# All.net
KiCad netlist of a schematic drawn in EAGLE
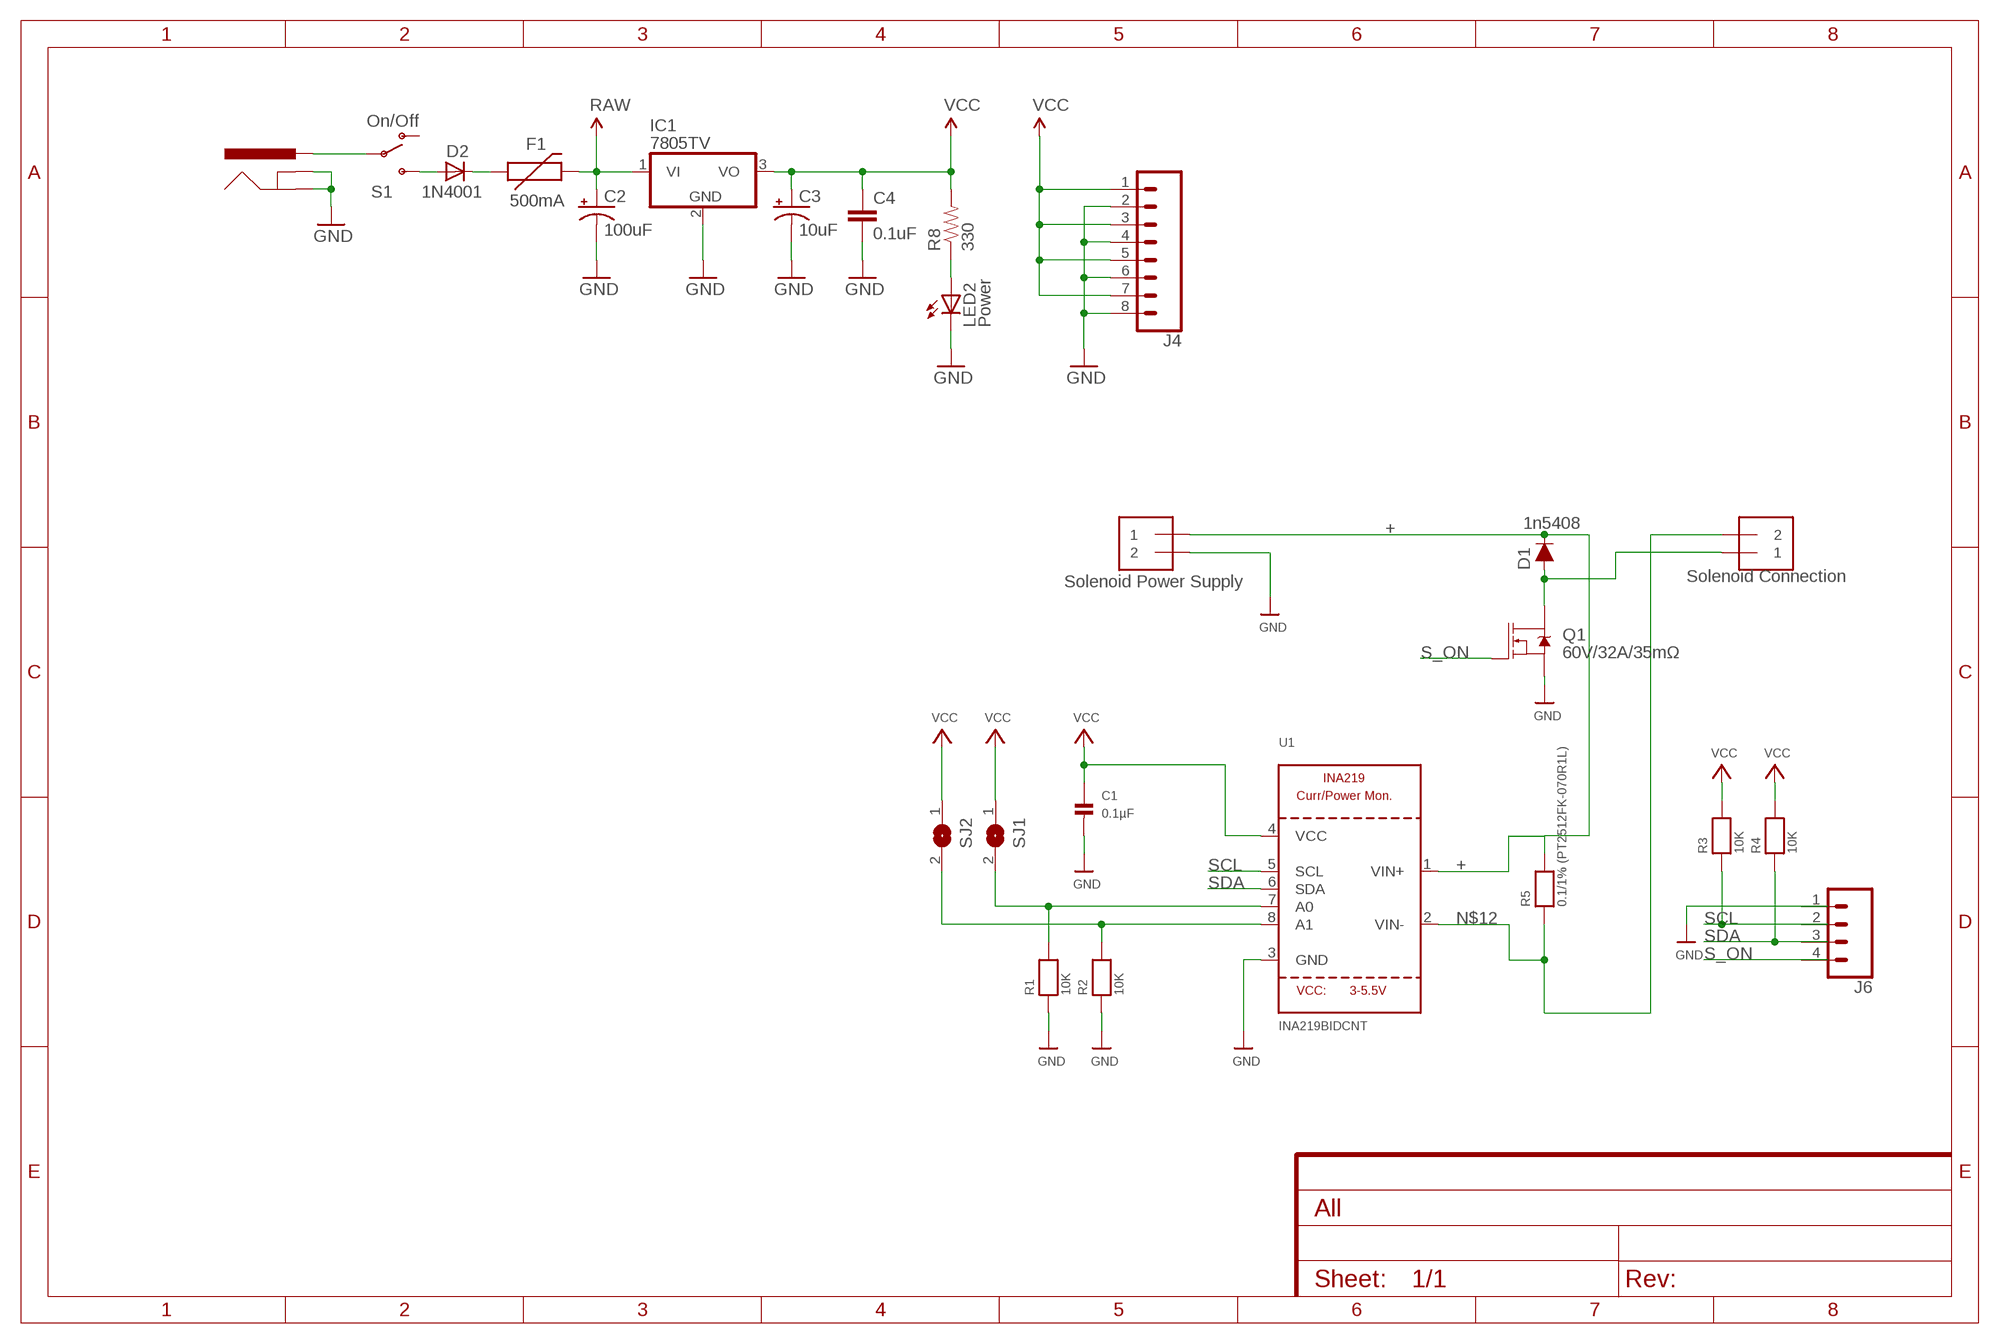
[diagram p0: schematic, sheet 1]

(export (version "E")
  (design (tool "Eeschema 10.0.6"))
  (components
    (comp (ref "C1")
      (value "0.1µF")
      (footprint "eagle-import:0805")
      (libsource (lib "eagle-import") (part "CAP_CERAMIC0805"))
    )
    (comp (ref "C2")
      (value "100uF")
      (footprint "eagle-import:CPOL-RADIAL-100UF-25V")
      (libsource (lib "eagle-import") (part "CAP_POLPTH1"))
    )
    (comp (ref "C3")
      (value "10uF")
      (footprint "eagle-import:CPOL-RADIAL-10UF-25V")
      (libsource (lib "eagle-import") (part "CAP_POLPTH2"))
    )
    (comp (ref "C4")
      (value "0.1uF")
      (footprint "eagle-import:CAP-PTH-SMALL2")
      (libsource (lib "eagle-import") (part "CAPPTH2"))
    )
    (comp (ref "D1")
      (value "DIODE-1N4148")
      (footprint "eagle-import:DIODE-1N4148")
      (fields (field (name "TEMP") "1n5408"))
      (libsource (lib "eagle-import") (part "DIODE-1N4148"))
    )
    (comp (ref "D2")
      (value "1N4001")
      (footprint "eagle-import:DIODE-0.4")
      (libsource (lib "eagle-import") (part "DIODEPTH"))
    )
    (comp (ref "F1")
      (value "500mA")
      (footprint "eagle-import:PTC")
      (libsource (lib "eagle-import") (part "PTCPTH"))
    )
    (comp (ref "IC1")
      (value "7805TV")
      (footprint "eagle-import:TO220V")
      (libsource (lib "eagle-import") (part "78TV05"))
    )
    (comp (ref "J1")
      (value "POWER_JACKPTH")
      (footprint "eagle-import:POWER_JACK_PTH")
      (libsource (lib "eagle-import") (part "POWER_JACKPTH"))
    )
    (comp (ref "J2")
      (value "TERMBLOCK_1X2-3.5MM")
      (footprint "eagle-import:1X2-3.5MM")
      (fields (field (name "TEMP") "Solenoid Power Supply"))
      (libsource (lib "eagle-import") (part "TERMBLOCK_1X2-3.5MM"))
    )
    (comp (ref "J3")
      (value "TERMBLOCK_1X2-3.5MM")
      (footprint "eagle-import:1X2-3.5MM")
      (fields (field (name "TEMP") "Solenoid Connection"))
      (libsource (lib "eagle-import") (part "TERMBLOCK_1X2-3.5MM"))
    )
    (comp (ref "J4")
      (value "CONN_08\"")
      (footprint "eagle-import:1X08")
      (libsource (lib "eagle-import") (part "CONN_08{dblquote}"))
    )
    (comp (ref "J6")
      (value "CONN_04")
      (footprint "eagle-import:1X04")
      (libsource (lib "eagle-import") (part "CONN_04"))
    )
    (comp (ref "LED2")
      (value "Power")
      (footprint "eagle-import:LED5MM")
      (libsource (lib "eagle-import") (part "LED5MM"))
    )
    (comp (ref "Q1")
      (value "60V/32A/35mΩ")
      (footprint "eagle-import:TO220V")
      (libsource (lib "eagle-import") (part "MOSFET-NCH-FQP30N06L"))
    )
    (comp (ref "R1")
      (value "10K")
      (footprint "eagle-import:0805")
      (libsource (lib "eagle-import") (part "RESISTOR0805"))
    )
    (comp (ref "R2")
      (value "10K")
      (footprint "eagle-import:0805")
      (libsource (lib "eagle-import") (part "RESISTOR0805"))
    )
    (comp (ref "R3")
      (value "10K")
      (footprint "eagle-import:0805")
      (libsource (lib "eagle-import") (part "RESISTOR0805"))
    )
    (comp (ref "R4")
      (value "10K")
      (footprint "eagle-import:0805")
      (libsource (lib "eagle-import") (part "RESISTOR0805"))
    )
    (comp (ref "R5")
      (value "0.1/1% (PT2512FK-070R1L)")
      (footprint "eagle-import:2512")
      (libsource (lib "eagle-import") (part "RESISTOR2512"))
    )
    (comp (ref "R8")
      (value "330")
      (footprint "eagle-import:AXIAL-0.3")
      (libsource (lib "eagle-import") (part "RESISTORPTH1"))
    )
    (comp (ref "S1")
      (value "On/Off")
      (footprint "eagle-import:SWITCH-SPST")
      (libsource (lib "eagle-import") (part "SWITCH-SPSTPTH"))
    )
    (comp (ref "SJ1")
      (value "SOLDERJUMPERREFLOW_NOPASTE")
      (footprint "eagle-import:SOLDERJUMPER_REFLOW_NOPASTE")
      (libsource (lib "eagle-import") (part "SOLDERJUMPERREFLOW_NOPASTE"))
    )
    (comp (ref "SJ2")
      (value "SOLDERJUMPERREFLOW_NOPASTE")
      (footprint "eagle-import:SOLDERJUMPER_REFLOW_NOPASTE")
      (libsource (lib "eagle-import") (part "SOLDERJUMPERREFLOW_NOPASTE"))
    )
    (comp (ref "U1")
      (value "INA219BIDCNT")
      (footprint "eagle-import:SOT23-8")
      (libsource (lib "eagle-import") (part "INA219"))
    )
  )
  (nets
    (net (code "1") (name "/+") (class "Default")
      (node (ref "D1") (pin "C") (pinfunction "C_C") (pintype "passive"))
      (node (ref "J2") (pin "1") (pinfunction "1_1") (pintype "passive"))
      (node (ref "R5") (pin "2") (pinfunction "2_2") (pintype "passive"))
      (node (ref "U1") (pin "1") (pinfunction "VIN+_1") (pintype "bidirectional"))
    )
    (net (code "2") (name "/N$12") (class "Default")
      (node (ref "J3") (pin "2") (pinfunction "2_2") (pintype "passive"))
      (node (ref "R5") (pin "1") (pinfunction "1_1") (pintype "passive"))
      (node (ref "U1") (pin "2") (pinfunction "VIN-_2") (pintype "bidirectional"))
    )
    (net (code "3") (name "/SCL") (class "Default")
      (node (ref "J6") (pin "2") (pinfunction "2_2") (pintype "passive"))
      (node (ref "R3") (pin "1") (pinfunction "1_1") (pintype "passive"))
      (node (ref "U1") (pin "5") (pinfunction "SCL_5") (pintype "bidirectional"))
    )
    (net (code "4") (name "/SDA") (class "Default")
      (node (ref "J6") (pin "3") (pinfunction "3_3") (pintype "passive"))
      (node (ref "R4") (pin "1") (pinfunction "1_1") (pintype "passive"))
      (node (ref "U1") (pin "6") (pinfunction "SDA_6") (pintype "bidirectional"))
    )
    (net (code "5") (name "/S_ON") (class "Default")
      (node (ref "J6") (pin "4") (pinfunction "4_4") (pintype "passive"))
      (node (ref "Q1") (pin "1") (pinfunction "G_1") (pintype "bidirectional"))
    )
    (net (code "6") (name "GND") (class "Default")
      (node (ref "C1") (pin "2") (pinfunction "P$2_2") (pintype "passive"))
      (node (ref "C2") (pin "2") (pinfunction "-_2") (pintype "passive"))
      (node (ref "C3") (pin "2") (pinfunction "-_2") (pintype "passive"))
      (node (ref "C4") (pin "2") (pinfunction "2_2") (pintype "passive"))
      (node (ref "IC1") (pin "2") (pinfunction "GND_2") (pintype "passive"))
      (node (ref "J1") (pin "GND") (pinfunction "GND_GND") (pintype "bidirectional"))
      (node (ref "J1") (pin "GNDBREAK") (pinfunction "GNDBREAK_GNDBREAK") (pintype "bidirectional"))
      (node (ref "J2") (pin "2") (pinfunction "2_2") (pintype "passive"))
      (node (ref "J4") (pin "2") (pinfunction "2_2") (pintype "passive"))
      (node (ref "J4") (pin "4") (pinfunction "4_4") (pintype "passive"))
      (node (ref "J4") (pin "6") (pinfunction "6_6") (pintype "passive"))
      (node (ref "J4") (pin "8") (pinfunction "8_8") (pintype "passive"))
      (node (ref "J6") (pin "1") (pinfunction "1_1") (pintype "passive"))
      (node (ref "LED2") (pin "K") (pinfunction "C_K") (pintype "passive"))
      (node (ref "Q1") (pin "3") (pinfunction "S_3") (pintype "bidirectional"))
      (node (ref "R1") (pin "1") (pinfunction "1_1") (pintype "passive"))
      (node (ref "R2") (pin "1") (pinfunction "1_1") (pintype "passive"))
      (node (ref "U1") (pin "3") (pinfunction "GND_3") (pintype "bidirectional"))
    )
    (net (code "7") (name "Net-(F1-1)") (class "Default")
      (node (ref "D2") (pin "C") (pinfunction "C_C") (pintype "passive"))
      (node (ref "F1") (pin "P$1") (pinfunction "1_P$1") (pintype "bidirectional"))
    )
    (net (code "8") (name "Net-(Q1-D)") (class "Default")
      (node (ref "D1") (pin "A") (pinfunction "A_A") (pintype "passive"))
      (node (ref "J3") (pin "1") (pinfunction "1_1") (pintype "passive"))
      (node (ref "Q1") (pin "2") (pinfunction "D_2") (pintype "bidirectional"))
    )
    (net (code "9") (name "Net-(R8-1)") (class "Default")
      (node (ref "LED2") (pin "A") (pinfunction "A_A") (pintype "passive"))
      (node (ref "R8") (pin "P$1") (pinfunction "1_P$1") (pintype "passive"))
    )
    (net (code "10") (name "Net-(S1-P)") (class "Default")
      (node (ref "J1") (pin "PWR") (pinfunction "PWR_PWR") (pintype "bidirectional"))
      (node (ref "S1") (pin "2") (pinfunction "P_2") (pintype "passive"))
    )
    (net (code "11") (name "Net-(S1-S)") (class "Default")
      (node (ref "D2") (pin "A") (pinfunction "A_A") (pintype "passive"))
      (node (ref "S1") (pin "3") (pinfunction "S_3") (pintype "passive"))
    )
    (net (code "12") (name "Net-(U1-A0)") (class "Default")
      (node (ref "R1") (pin "2") (pinfunction "2_2") (pintype "passive"))
      (node (ref "SJ1") (pin "2") (pinfunction "2_2") (pintype "passive"))
      (node (ref "U1") (pin "7") (pinfunction "A0_7") (pintype "bidirectional"))
    )
    (net (code "13") (name "Net-(U1-A1)") (class "Default")
      (node (ref "R2") (pin "2") (pinfunction "2_2") (pintype "passive"))
      (node (ref "SJ2") (pin "2") (pinfunction "2_2") (pintype "passive"))
      (node (ref "U1") (pin "8") (pinfunction "A1_8") (pintype "bidirectional"))
    )
    (net (code "14") (name "RAW") (class "Default")
      (node (ref "C2") (pin "1") (pinfunction "+_1") (pintype "passive"))
      (node (ref "F1") (pin "P$2") (pinfunction "2_P$2") (pintype "bidirectional"))
      (node (ref "IC1") (pin "1") (pinfunction "VI_1") (pintype "input"))
    )
    (net (code "15") (name "VCC") (class "Default")
      (node (ref "C1") (pin "1") (pinfunction "P$1_1") (pintype "passive"))
      (node (ref "C3") (pin "1") (pinfunction "+_1") (pintype "passive"))
      (node (ref "C4") (pin "1") (pinfunction "1_1") (pintype "passive"))
      (node (ref "IC1") (pin "3") (pinfunction "VO_3") (pintype "passive"))
      (node (ref "J4") (pin "1") (pinfunction "1_1") (pintype "passive"))
      (node (ref "J4") (pin "3") (pinfunction "3_3") (pintype "passive"))
      (node (ref "J4") (pin "5") (pinfunction "5_5") (pintype "passive"))
      (node (ref "J4") (pin "7") (pinfunction "7_7") (pintype "passive"))
      (node (ref "R3") (pin "2") (pinfunction "2_2") (pintype "passive"))
      (node (ref "R4") (pin "2") (pinfunction "2_2") (pintype "passive"))
      (node (ref "R8") (pin "P$2") (pinfunction "2_P$2") (pintype "passive"))
      (node (ref "SJ1") (pin "1") (pinfunction "1_1") (pintype "passive"))
      (node (ref "SJ2") (pin "1") (pinfunction "1_1") (pintype "passive"))
      (node (ref "U1") (pin "4") (pinfunction "VCC_4") (pintype "bidirectional"))
    )
    (net (code "16") (name "unconnected-(S1-O-Pad1)") (class "Default")
      (node (ref "S1") (pin "1") (pinfunction "O_1") (pintype "passive"))
    )
  )
)
